# P07_IO_SWITCH_JTAG_MICRO_SD.net
KiCad netlist of a schematic drawn in Altium Designer
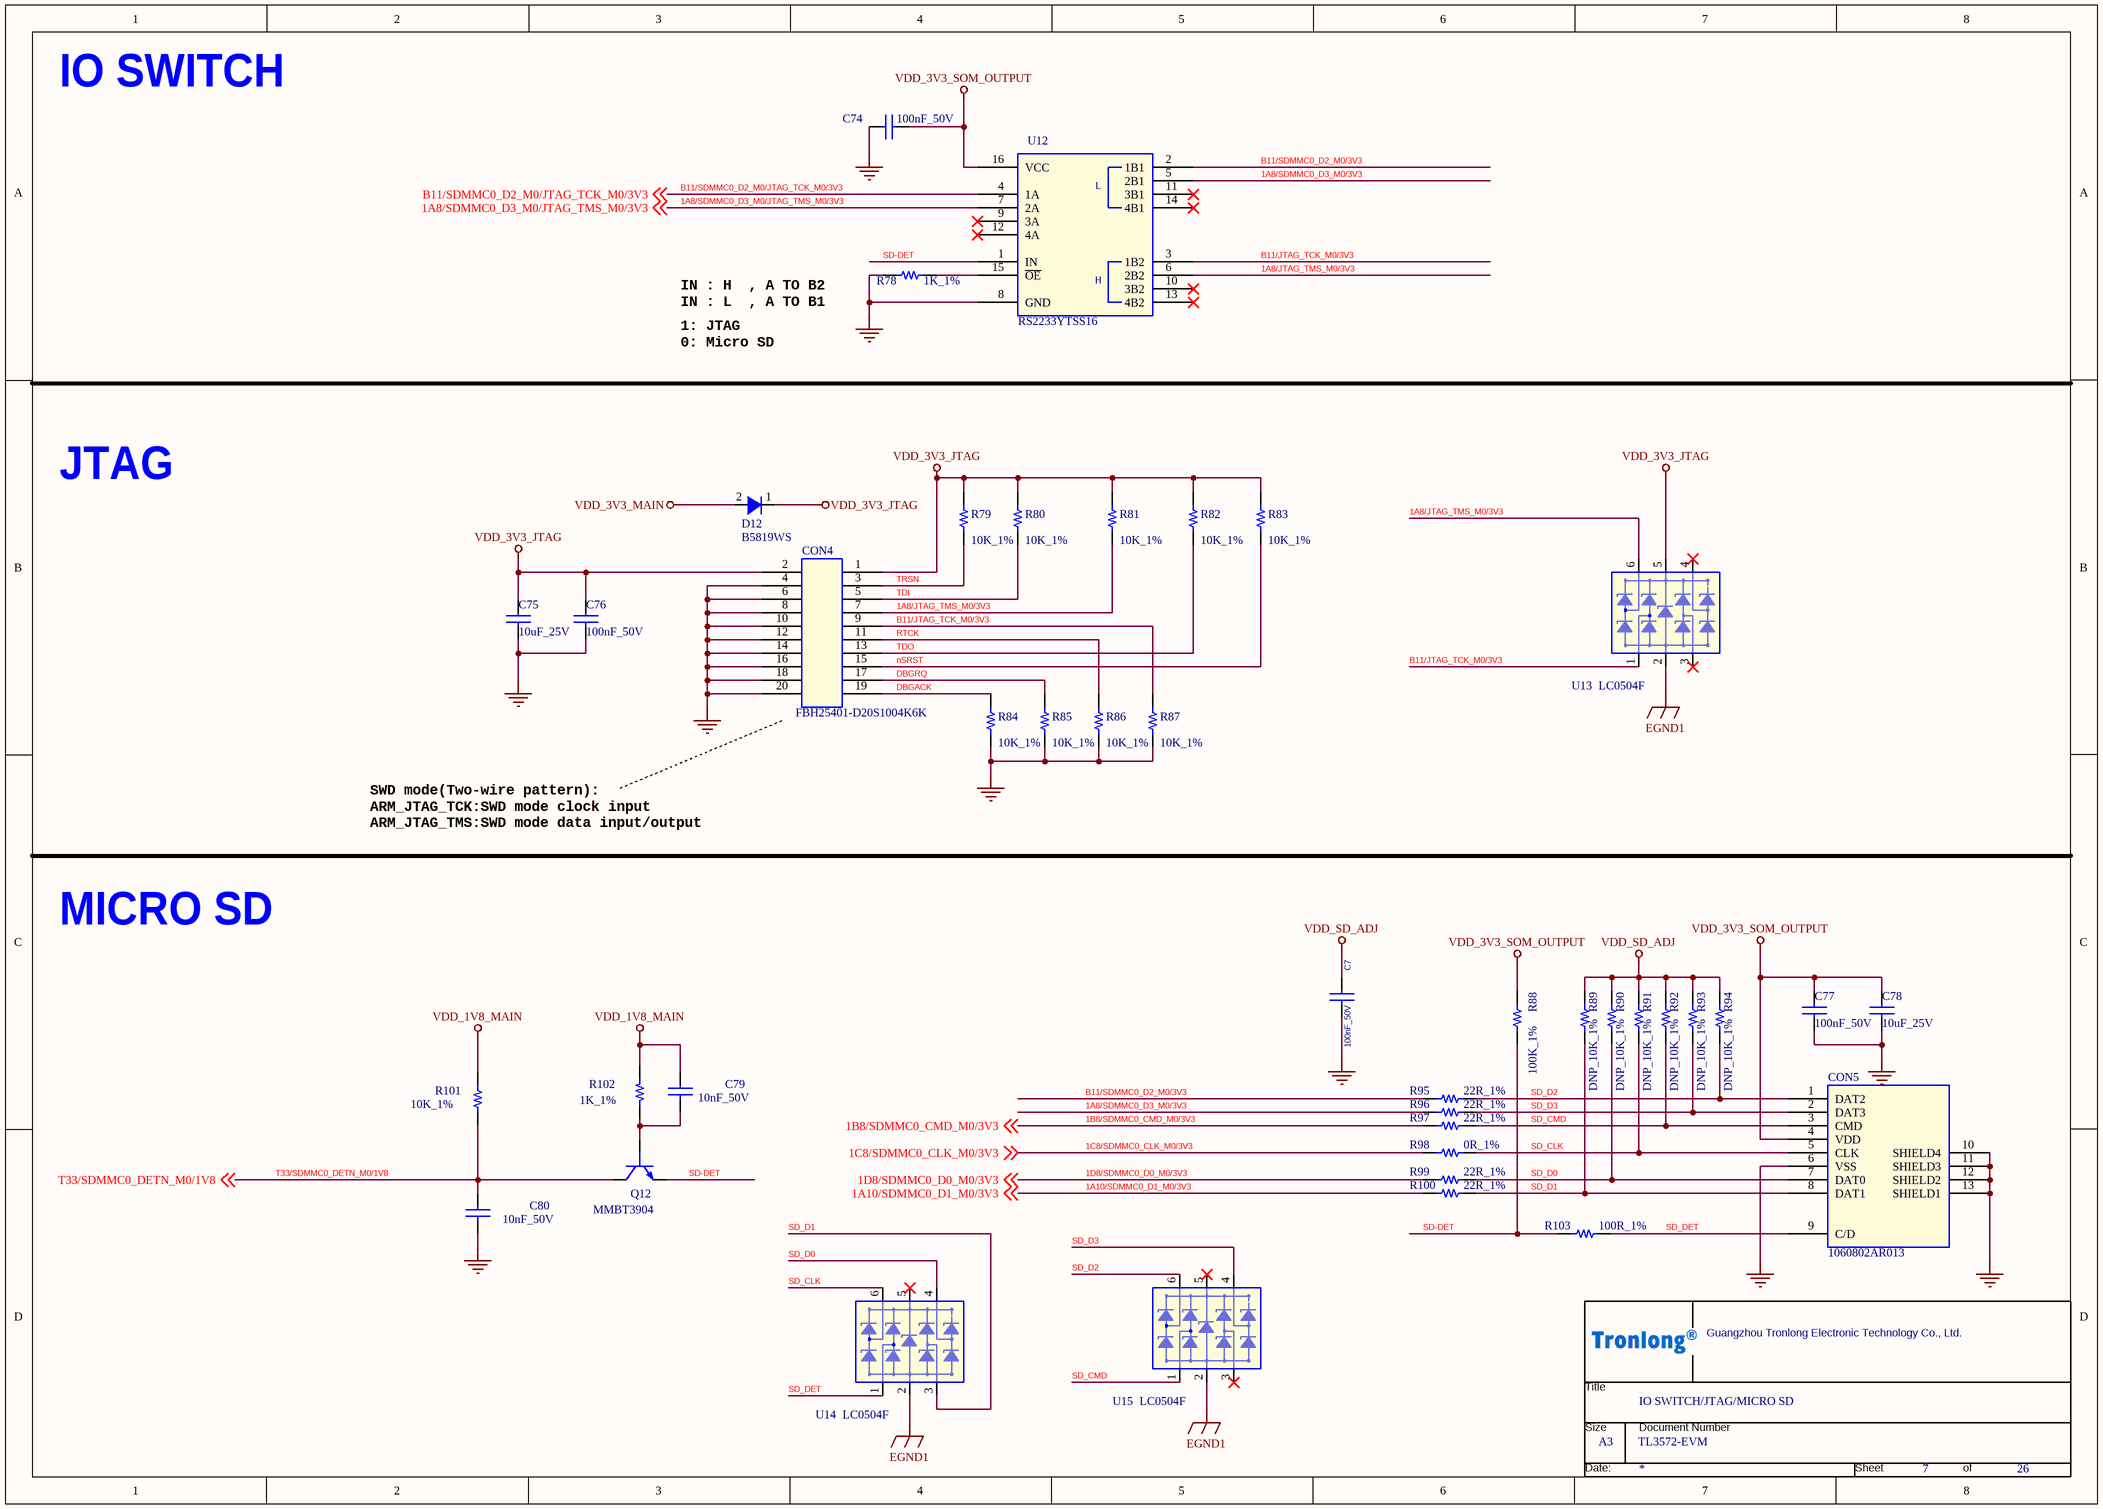
[diagram p0: P07_IO SWITCH_JTAG_MICRO SD.SchDoc]

(export (version "E")
  (design (tool "Eeschema 10.0.6"))
  (components
    (comp (ref "*")
      (value "TL_NEW")
      (fields
        (field (name "PAGE COUNT") "26")
        (field (name "PAGE NUMBER") "7")
        (field (name "PAGE SIZE") "A3")
        (field (name "ORGNAME") "Guangzhou Tronlong Electronic Technology Co., Ltd.")
        (field (name "TITLE") "IO SWITCH/JTAG/MICRO SD")
        (field (name "DOC") "TL3572-EVM")
      )
      (libsource (lib "*") (part "TL_NEW"))
    )
    (comp (ref "C7")
      (value "100nF_50V")
      (footprint "C0402")
      (description "贴片陶瓷电容,100nF,10%,50V,X7R")
      (fields
        (field (name "MANUFACTURER PARTNUMBER") "0402B104K500NT")
        (field (name "MANUFACTURER") "广东风华高新科技股份有限公司（FH）")
      )
      (libsource (lib "*") (part "CAP NP_Dup2"))
    )
    (comp (ref "C74")
      (value "100nF_50V")
      (footprint "C0402")
      (description "贴片陶瓷电容,100nF,10%,50V,X7R")
      (fields
        (field (name "MANUFACTURER") "广东风华高新科技股份有限公司（FH）")
        (field (name "MANUFACTURER PARTNUMBER") "0402B104K500NT")
      )
      (libsource (lib "*") (part "CAP NP_Dup2"))
    )
    (comp (ref "C75")
      (value "10uF_25V")
      (footprint "C0603")
      (description "贴片陶瓷电容,10uF,20%,25V,X5R")
      (fields
        (field (name "MANUFACTURER PARTNUMBER") "0603X106M250NT")
        (field (name "MANUFACTURER") "广东风华高新科技股份有限公司（FH）")
      )
      (libsource (lib "*") (part "CAP NP_Dup2"))
    )
    (comp (ref "C76")
      (value "100nF_50V")
      (footprint "C0402")
      (description "贴片陶瓷电容,100nF,10%,50V,X7R")
      (fields
        (field (name "MANUFACTURER") "广东风华高新科技股份有限公司（FH）")
        (field (name "MANUFACTURER PARTNUMBER") "0402B104K500NT")
      )
      (libsource (lib "*") (part "CAP NP_Dup2"))
    )
    (comp (ref "C77")
      (value "100nF_50V")
      (footprint "C0402")
      (description "贴片陶瓷电容,100nF,10%,50V,X7R")
      (fields
        (field (name "MANUFACTURER") "广东风华高新科技股份有限公司（FH）")
        (field (name "MANUFACTURER PARTNUMBER") "0402B104K500NT")
      )
      (libsource (lib "*") (part "CAP NP_Dup2"))
    )
    (comp (ref "C78")
      (value "10uF_25V")
      (footprint "C0603")
      (description "贴片陶瓷电容,10uF,20%,25V,X5R")
      (fields
        (field (name "MANUFACTURER PARTNUMBER") "0603X106M250NT")
        (field (name "MANUFACTURER") "广东风华高新科技股份有限公司（FH）")
      )
      (libsource (lib "*") (part "CAP NP_Dup2"))
    )
    (comp (ref "C79")
      (value "10nF_50V")
      (footprint "C0402")
      (description "贴片陶瓷电容,10nF,10%,50V,X7R")
      (fields
        (field (name "MANUFACTURER PARTNUMBER") "0402B103K500NT")
        (field (name "MANUFACTURER") "广东风华高新科技股份有限公司（FH）")
      )
      (libsource (lib "*") (part "CAP NP_Dup3"))
    )
    (comp (ref "C80")
      (value "10nF_50V")
      (footprint "C0402")
      (description "贴片陶瓷电容,10nF,10%,50V,X7R")
      (fields
        (field (name "MANUFACTURER PARTNUMBER") "0402B103K500NT")
        (field (name "MANUFACTURER") "广东风华高新科技股份有限公司（FH）")
      )
      (libsource (lib "*") (part "CAP NP_Dup3"))
    )
    (comp (ref "CON4")
      (value "FBH25401-D20S1004K6K")
      (footprint "con_2d54_2x10_th_box_90")
      (description "简易牛角座,2x10P,2.54mm,公座,黑色,180度")
      (fields (field (name "MANUFACTURER") "深圳特思嘉工业电子有限公司（TXGA）"))
      (libsource (lib "*") (part "CON20A"))
    )
    (comp (ref "CON5")
      (value "1060802AR013")
      (footprint "CON_TF_CARD")
      (description "Micro SD卡座,9P,自弹,贴片")
      (fields (field (name "MANUFACTURER") "广州高炬电子科技有限公司（gorchi）"))
      (libsource (lib "*") (part "PROCONN SDC009-52-D_3"))
    )
    (comp (ref "D12")
      (value "B5819WS")
      (footprint "SOD-323")
      (description "肖特基二极管,VR=40V,IF=1A,VF=0.6V@1A")
      (fields (field (name "MFR") "On Semiconductor") (field (name "TIINTPARTNUMBER") "1E0013"))
      (libsource (lib "*") (part "Diode200mA250V_2"))
    )
    (comp (ref "Q12")
      (value "MMBT3904")
      (footprint "SOT23-3_DBZ3")
      (description "BJT,NPN,Vceo=40V,Ic=200mA,fT=300MHz,PD=200mW")
      (fields (field (name "MANUFACTURER") "江苏长晶科技股份有限公司（JSCJ）"))
      (libsource (lib "*") (part "MMBT3904/SOT"))
    )
    (comp (ref "R78")
      (value "1K_1%")
      (footprint "R0603")
      (description "贴片电阻,1K,±1%,1/10W")
      (fields
        (field (name "MANUFACTURER") "广东风华高新科技股份有限公司（FH）")
        (field (name "MANUFACTURER PARTNUMBER") "RS-03K1001FT")
      )
      (libsource (lib "*") (part "Resistor_Dup3"))
    )
    (comp (ref "R79")
      (value "10K_1%")
      (footprint "R0402")
      (description "贴片电阻,10K,±1%,1/16W")
      (fields
        (field (name "MANUFACTURER") "广东风华高新科技股份有限公司（FH）")
        (field (name "MANUFACTURER PARTNUMBER") "RC-02K1002FT")
      )
      (libsource (lib "*") (part "Resistor_Dup3"))
    )
    (comp (ref "R80")
      (value "10K_1%")
      (footprint "R0402")
      (description "贴片电阻,10K,±1%,1/16W")
      (fields
        (field (name "MANUFACTURER PARTNUMBER") "RC-02K1002FT")
        (field (name "MANUFACTURER") "广东风华高新科技股份有限公司（FH）")
      )
      (libsource (lib "*") (part "Resistor_Dup3"))
    )
    (comp (ref "R81")
      (value "10K_1%")
      (footprint "R0402")
      (description "贴片电阻,10K,±1%,1/16W")
      (fields
        (field (name "MANUFACTURER PARTNUMBER") "RC-02K1002FT")
        (field (name "MANUFACTURER") "广东风华高新科技股份有限公司（FH）")
      )
      (libsource (lib "*") (part "Resistor_Dup3"))
    )
    (comp (ref "R82")
      (value "10K_1%")
      (footprint "R0402")
      (description "贴片电阻,10K,±1%,1/16W")
      (fields
        (field (name "MANUFACTURER PARTNUMBER") "RC-02K1002FT")
        (field (name "MANUFACTURER") "广东风华高新科技股份有限公司（FH）")
      )
      (libsource (lib "*") (part "Resistor_Dup3"))
    )
    (comp (ref "R83")
      (value "10K_1%")
      (footprint "R0402")
      (description "贴片电阻,10K,±1%,1/16W")
      (fields
        (field (name "MANUFACTURER") "广东风华高新科技股份有限公司（FH）")
        (field (name "MANUFACTURER PARTNUMBER") "RC-02K1002FT")
      )
      (libsource (lib "*") (part "Resistor_Dup3"))
    )
    (comp (ref "R84")
      (value "10K_1%")
      (footprint "R0402")
      (description "贴片电阻,10K,±1%,1/16W")
      (fields
        (field (name "MANUFACTURER") "广东风华高新科技股份有限公司（FH）")
        (field (name "MANUFACTURER PARTNUMBER") "RC-02K1002FT")
      )
      (libsource (lib "*") (part "Resistor_Dup3"))
    )
    (comp (ref "R85")
      (value "10K_1%")
      (footprint "R0402")
      (description "贴片电阻,10K,±1%,1/16W")
      (fields
        (field (name "MANUFACTURER") "广东风华高新科技股份有限公司（FH）")
        (field (name "MANUFACTURER PARTNUMBER") "RC-02K1002FT")
      )
      (libsource (lib "*") (part "Resistor_Dup3"))
    )
    (comp (ref "R86")
      (value "10K_1%")
      (footprint "R0402")
      (description "贴片电阻,10K,±1%,1/16W")
      (fields
        (field (name "MANUFACTURER PARTNUMBER") "RC-02K1002FT")
        (field (name "MANUFACTURER") "广东风华高新科技股份有限公司（FH）")
      )
      (libsource (lib "*") (part "Resistor_Dup3"))
    )
    (comp (ref "R87")
      (value "10K_1%")
      (footprint "R0402")
      (description "贴片电阻,10K,±1%,1/16W")
      (fields
        (field (name "MANUFACTURER PARTNUMBER") "RC-02K1002FT")
        (field (name "MANUFACTURER") "广东风华高新科技股份有限公司（FH）")
      )
      (libsource (lib "*") (part "Resistor_Dup3"))
    )
    (comp (ref "R88")
      (value "100K_1%")
      (footprint "R0402")
      (description "RC0402FR-07100KL,0402WGF1003TCE")
      (fields
        (field (name "MANUFACTURER PARTNUMBER") "100K,±1%,R0402,≥1/16W")
        (field (name "MANUFACTURER") "广州创龙")
      )
      (libsource (lib "*") (part "Resistor_Dup3"))
    )
    (comp (ref "R89")
      (value "DNP_10K_1%")
      (footprint "R0402")
      (description "贴片电阻,10K,±1%,1/16W")
      (fields
        (field (name "MANUFACTURER") "广东风华高新科技股份有限公司（FH）")
        (field (name "MANUFACTURER PARTNUMBER") "RC-02K1002FT")
      )
      (libsource (lib "*") (part "Resistor_Dup3"))
    )
    (comp (ref "R90")
      (value "DNP_10K_1%")
      (footprint "R0402")
      (description "贴片电阻,10K,±1%,1/16W")
      (fields
        (field (name "MANUFACTURER") "广东风华高新科技股份有限公司（FH）")
        (field (name "MANUFACTURER PARTNUMBER") "RC-02K1002FT")
      )
      (libsource (lib "*") (part "Resistor_Dup3"))
    )
    (comp (ref "R91")
      (value "DNP_10K_1%")
      (footprint "R0402")
      (description "贴片电阻,10K,±1%,1/16W")
      (fields
        (field (name "MANUFACTURER") "广东风华高新科技股份有限公司（FH）")
        (field (name "MANUFACTURER PARTNUMBER") "RC-02K1002FT")
      )
      (libsource (lib "*") (part "Resistor_Dup3"))
    )
    (comp (ref "R92")
      (value "DNP_10K_1%")
      (footprint "R0402")
      (description "贴片电阻,10K,±1%,1/16W")
      (fields
        (field (name "MANUFACTURER PARTNUMBER") "RC-02K1002FT")
        (field (name "MANUFACTURER") "广东风华高新科技股份有限公司（FH）")
      )
      (libsource (lib "*") (part "Resistor_Dup3"))
    )
    (comp (ref "R93")
      (value "DNP_10K_1%")
      (footprint "R0402")
      (description "贴片电阻,10K,±1%,1/16W")
      (fields
        (field (name "MANUFACTURER") "广东风华高新科技股份有限公司（FH）")
        (field (name "MANUFACTURER PARTNUMBER") "RC-02K1002FT")
      )
      (libsource (lib "*") (part "Resistor_Dup3"))
    )
    (comp (ref "R94")
      (value "DNP_10K_1%")
      (footprint "R0402")
      (description "贴片电阻,10K,±1%,1/16W")
      (fields
        (field (name "MANUFACTURER") "广东风华高新科技股份有限公司（FH）")
        (field (name "MANUFACTURER PARTNUMBER") "RC-02K1002FT")
      )
      (libsource (lib "*") (part "Resistor_Dup3"))
    )
    (comp (ref "R95")
      (value "22R_1%")
      (footprint "R0402")
      (description "贴片电阻,22R,±1%,1/16W")
      (fields
        (field (name "MANUFACTURER PARTNUMBER") "RC-02K22R0FT")
        (field (name "MANUFACTURER") "广东风华高新科技股份有限公司（FH）")
      )
      (libsource (lib "*") (part "Resistor_Dup3"))
    )
    (comp (ref "R96")
      (value "22R_1%")
      (footprint "R0402")
      (description "贴片电阻,22R,±1%,1/16W")
      (fields
        (field (name "MANUFACTURER PARTNUMBER") "RC-02K22R0FT")
        (field (name "MANUFACTURER") "广东风华高新科技股份有限公司（FH）")
      )
      (libsource (lib "*") (part "Resistor_Dup3"))
    )
    (comp (ref "R97")
      (value "22R_1%")
      (footprint "R0402")
      (description "贴片电阻,22R,±1%,1/16W")
      (fields
        (field (name "MANUFACTURER PARTNUMBER") "RC-02K22R0FT")
        (field (name "MANUFACTURER") "广东风华高新科技股份有限公司（FH）")
      )
      (libsource (lib "*") (part "Resistor_Dup3"))
    )
    (comp (ref "R98")
      (value "0R_1%")
      (footprint "R0402")
      (description "贴片电阻,0R,±1%,1/16W")
      (fields
        (field (name "MANUFACTURER") "广东风华高新科技股份有限公司（FH）")
        (field (name "MANUFACTURER PARTNUMBER") "RC-02000FT")
      )
      (libsource (lib "*") (part "Resistor_Dup3"))
    )
    (comp (ref "R99")
      (value "22R_1%")
      (footprint "R0402")
      (description "贴片电阻,22R,±1%,1/16W")
      (fields
        (field (name "MANUFACTURER") "广东风华高新科技股份有限公司（FH）")
        (field (name "MANUFACTURER PARTNUMBER") "RC-02K22R0FT")
      )
      (libsource (lib "*") (part "Resistor_Dup3"))
    )
    (comp (ref "R100")
      (value "22R_1%")
      (footprint "R0402")
      (description "贴片电阻,22R,±1%,1/16W")
      (fields
        (field (name "MANUFACTURER PARTNUMBER") "RC-02K22R0FT")
        (field (name "MANUFACTURER") "广东风华高新科技股份有限公司（FH）")
      )
      (libsource (lib "*") (part "Resistor_Dup3"))
    )
    (comp (ref "R101")
      (value "10K_1%")
      (footprint "R0402")
      (description "贴片电阻,10K,±1%,1/16W")
      (fields
        (field (name "MANUFACTURER") "广东风华高新科技股份有限公司（FH）")
        (field (name "MANUFACTURER PARTNUMBER") "RC-02K1002FT")
      )
      (libsource (lib "*") (part "Resistor_Dup4"))
    )
    (comp (ref "R102")
      (value "1K_1%")
      (footprint "R0603")
      (description "贴片电阻,1K,±1%,1/10W")
      (fields
        (field (name "MANUFACTURER PARTNUMBER") "RS-03K1001FT")
        (field (name "MANUFACTURER") "广东风华高新科技股份有限公司（FH）")
      )
      (libsource (lib "*") (part "Resistor_Dup4"))
    )
    (comp (ref "R103")
      (value "100R_1%")
      (footprint "R0402")
      (description "贴片电阻,100R,±1%,1/16W")
      (fields
        (field (name "MANUFACTURER") "广东风华高新科技股份有限公司（FH）")
        (field (name "MANUFACTURER PARTNUMBER") "RC-02K1000FT")
      )
      (libsource (lib "*") (part "Resistor_Dup4"))
    )
    (comp (ref "U12")
      (value "RS2233YTSS16")
      (footprint "TSSOP16")
      (description "4通道模拟开关")
      (fields (field (name "MANUFACTURER") "江苏润石科技有限公司（RUNIC）"))
      (libsource (lib "*") (part "TS3A5018DR_2"))
    )
    (comp (ref "U13")
      (value "LC0504F")
      (footprint "SOT363")
      (description "ESD二极管,VRWM=5V,VBR=6V,四组,单向,8KV,15KV")
      (fields
        (field (name "MANUFACTURER PART NUMBER") "PRTR5V0U4Y")
        (field (name "MANUFACTURER") "上海雷卯电子科技有限公司（Leiditech）")
      )
      (libsource (lib "*") (part "PRTR5V0U4Y_0"))
    )
    (comp (ref "U14")
      (value "LC0504F")
      (footprint "SOT363")
      (description "ESD二极管,VRWM=5V,VBR=6V,四组,单向,8KV,15KV")
      (fields
        (field (name "MANUFACTURER") "上海雷卯电子科技有限公司（Leiditech）")
        (field (name "MANUFACTURER PART NUMBER") "PRTR5V0U4Y")
      )
      (libsource (lib "*") (part "PRTR5V0U4Y_0"))
    )
    (comp (ref "U15")
      (value "LC0504F")
      (footprint "SOT363")
      (description "ESD二极管,VRWM=5V,VBR=6V,四组,单向,8KV,15KV")
      (fields
        (field (name "MANUFACTURER PART NUMBER") "PRTR5V0U4Y")
        (field (name "MANUFACTURER") "上海雷卯电子科技有限公司（Leiditech）")
      )
      (libsource (lib "*") (part "PRTR5V0U4Y_0"))
    )
  )
  (nets
    (net (code "1") (name "/1A8{slash}JTAG_TMS_M0{slash}3V3") (class "Default")
      (node (ref "CON4") (pin "7") (pinfunction "7_7") (pintype "passive"))
      (node (ref "R81") (pin "2") (pinfunction "2_2") (pintype "passive"))
      (node (ref "U12") (pin "6") (pinfunction "2B2_6") (pintype "passive"))
      (node (ref "U13") (pin "6") (pinfunction "6_6") (pintype "passive"))
    )
    (net (code "2") (name "/1A8{slash}SDMMC0_D3_M0{slash}3V3") (class "Default")
      (node (ref "R96") (pin "1") (pinfunction "1_1") (pintype "passive"))
      (node (ref "U12") (pin "5") (pinfunction "2B1_5") (pintype "passive"))
    )
    (net (code "3") (name "/B11{slash}JTAG_TCK_M0{slash}3V3") (class "Default")
      (node (ref "CON4") (pin "9") (pinfunction "9_9") (pintype "passive"))
      (node (ref "R87") (pin "1") (pinfunction "1_1") (pintype "passive"))
      (node (ref "U12") (pin "3") (pinfunction "1B2_3") (pintype "passive"))
      (node (ref "U13") (pin "1") (pinfunction "1_1") (pintype "passive"))
    )
    (net (code "4") (name "/B11{slash}SDMMC0_D2_M0{slash}3V3") (class "Default")
      (node (ref "R95") (pin "1") (pinfunction "1_1") (pintype "passive"))
      (node (ref "U12") (pin "2") (pinfunction "1B1_2") (pintype "passive"))
    )
    (net (code "5") (name "/DBGACK") (class "Default")
      (node (ref "CON4") (pin "19") (pinfunction "19_19") (pintype "passive"))
      (node (ref "R84") (pin "1") (pinfunction "1_1") (pintype "passive"))
    )
    (net (code "6") (name "/DBGRQ") (class "Default")
      (node (ref "CON4") (pin "17") (pinfunction "17_17") (pintype "passive"))
      (node (ref "R85") (pin "1") (pinfunction "1_1") (pintype "passive"))
    )
    (net (code "7") (name "/RTCK") (class "Default")
      (node (ref "CON4") (pin "11") (pinfunction "11_11") (pintype "passive"))
      (node (ref "R86") (pin "1") (pinfunction "1_1") (pintype "passive"))
    )
    (net (code "8") (name "/SD-DET") (class "Default")
      (node (ref "Q12") (pin "2") (pinfunction "E_2") (pintype "passive"))
      (node (ref "R103") (pin "1") (pinfunction "1_1") (pintype "passive"))
      (node (ref "R88") (pin "2") (pinfunction "2_2") (pintype "passive"))
      (node (ref "U12") (pin "1") (pinfunction "IN_1") (pintype "passive"))
    )
    (net (code "9") (name "/SD_CLK") (class "Default")
      (node (ref "CON5") (pin "5") (pinfunction "CLK_5") (pintype "passive"))
      (node (ref "R91") (pin "2") (pinfunction "2_2") (pintype "passive"))
      (node (ref "R98") (pin "2") (pinfunction "2_2") (pintype "passive"))
      (node (ref "U14") (pin "6") (pinfunction "6_6") (pintype "passive"))
    )
    (net (code "10") (name "/SD_CMD") (class "Default")
      (node (ref "CON5") (pin "3") (pinfunction "CMD_3") (pintype "passive"))
      (node (ref "R92") (pin "2") (pinfunction "2_2") (pintype "passive"))
      (node (ref "R97") (pin "2") (pinfunction "2_2") (pintype "passive"))
      (node (ref "U15") (pin "1") (pinfunction "1_1") (pintype "passive"))
    )
    (net (code "11") (name "/SD_D0") (class "Default")
      (node (ref "CON5") (pin "7") (pinfunction "DAT0_7") (pintype "passive"))
      (node (ref "R90") (pin "2") (pinfunction "2_2") (pintype "passive"))
      (node (ref "R99") (pin "2") (pinfunction "2_2") (pintype "passive"))
      (node (ref "U14") (pin "4") (pinfunction "4_4") (pintype "passive"))
    )
    (net (code "12") (name "/SD_D1") (class "Default")
      (node (ref "CON5") (pin "8") (pinfunction "DAT1_8") (pintype "passive"))
      (node (ref "R100") (pin "2") (pinfunction "2_2") (pintype "passive"))
      (node (ref "R89") (pin "2") (pinfunction "2_2") (pintype "passive"))
      (node (ref "U14") (pin "3") (pinfunction "3_3") (pintype "passive"))
    )
    (net (code "13") (name "/SD_D2") (class "Default")
      (node (ref "CON5") (pin "1") (pinfunction "DAT2_1") (pintype "passive"))
      (node (ref "R94") (pin "2") (pinfunction "2_2") (pintype "passive"))
      (node (ref "R95") (pin "2") (pinfunction "2_2") (pintype "passive"))
      (node (ref "U15") (pin "6") (pinfunction "6_6") (pintype "passive"))
    )
    (net (code "14") (name "/SD_D3") (class "Default")
      (node (ref "CON5") (pin "2") (pinfunction "DAT3_2") (pintype "passive"))
      (node (ref "R93") (pin "2") (pinfunction "2_2") (pintype "passive"))
      (node (ref "R96") (pin "2") (pinfunction "2_2") (pintype "passive"))
      (node (ref "U15") (pin "4") (pinfunction "4_4") (pintype "passive"))
    )
    (net (code "15") (name "/SD_DET") (class "Default")
      (node (ref "CON5") (pin "9") (pinfunction "C/D_9") (pintype "passive"))
      (node (ref "R103") (pin "2") (pinfunction "2_2") (pintype "passive"))
      (node (ref "U14") (pin "1") (pinfunction "1_1") (pintype "passive"))
    )
    (net (code "16") (name "/TDI") (class "Default")
      (node (ref "CON4") (pin "5") (pinfunction "5_5") (pintype "passive"))
      (node (ref "R80") (pin "2") (pinfunction "2_2") (pintype "passive"))
    )
    (net (code "17") (name "/TDO") (class "Default")
      (node (ref "CON4") (pin "13") (pinfunction "13_13") (pintype "passive"))
      (node (ref "R82") (pin "2") (pinfunction "2_2") (pintype "passive"))
    )
    (net (code "18") (name "/TRSN") (class "Default")
      (node (ref "CON4") (pin "3") (pinfunction "3_3") (pintype "passive"))
      (node (ref "R79") (pin "2") (pinfunction "2_2") (pintype "passive"))
    )
    (net (code "19") (name "/nSRST") (class "Default")
      (node (ref "CON4") (pin "15") (pinfunction "15_15") (pintype "passive"))
      (node (ref "R83") (pin "2") (pinfunction "2_2") (pintype "passive"))
    )
    (net (code "20") (name "1A8{slash}SDMMC0_D3_M0{slash}JTAG_TMS_M0{slash}3V3") (class "Default")
      (node (ref "U12") (pin "7") (pinfunction "2A_7") (pintype "passive"))
    )
    (net (code "21") (name "1A10{slash}SDMMC0_D1_M0{slash}3V3") (class "Default")
      (node (ref "R100") (pin "1") (pinfunction "1_1") (pintype "passive"))
    )
    (net (code "22") (name "1B8{slash}SDMMC0_CMD_M0{slash}3V3") (class "Default")
      (node (ref "R97") (pin "1") (pinfunction "1_1") (pintype "passive"))
    )
    (net (code "23") (name "1C8{slash}SDMMC0_CLK_M0{slash}3V3") (class "Default")
      (node (ref "R98") (pin "1") (pinfunction "1_1") (pintype "passive"))
    )
    (net (code "24") (name "1D8{slash}SDMMC0_D0_M0{slash}3V3") (class "Default")
      (node (ref "R99") (pin "1") (pinfunction "1_1") (pintype "passive"))
    )
    (net (code "25") (name "B11{slash}SDMMC0_D2_M0{slash}JTAG_TCK_M0{slash}3V3") (class "Default")
      (node (ref "U12") (pin "4") (pinfunction "1A_4") (pintype "passive"))
    )
    (net (code "26") (name "EGND1") (class "Default")
      (node (ref "U13") (pin "2") (pinfunction "2_2") (pintype "passive"))
      (node (ref "U14") (pin "2") (pinfunction "2_2") (pintype "passive"))
      (node (ref "U15") (pin "2") (pinfunction "2_2") (pintype "passive"))
    )
    (net (code "27") (name "GND") (class "Default")
      (node (ref "C7") (pin "2") (pinfunction "2_2") (pintype "passive"))
      (node (ref "C74") (pin "1") (pinfunction "1_1") (pintype "passive"))
      (node (ref "C75") (pin "2") (pinfunction "2_2") (pintype "passive"))
      (node (ref "C76") (pin "2") (pinfunction "2_2") (pintype "passive"))
      (node (ref "C77") (pin "2") (pinfunction "2_2") (pintype "passive"))
      (node (ref "C78") (pin "2") (pinfunction "2_2") (pintype "passive"))
      (node (ref "C80") (pin "2") (pinfunction "2_2") (pintype "passive"))
      (node (ref "CON4") (pin "10") (pinfunction "10_10") (pintype "passive"))
      (node (ref "CON4") (pin "12") (pinfunction "12_12") (pintype "passive"))
      (node (ref "CON4") (pin "14") (pinfunction "14_14") (pintype "passive"))
      (node (ref "CON4") (pin "16") (pinfunction "16_16") (pintype "passive"))
      (node (ref "CON4") (pin "18") (pinfunction "18_18") (pintype "passive"))
      (node (ref "CON4") (pin "20") (pinfunction "20_20") (pintype "passive"))
      (node (ref "CON4") (pin "4") (pinfunction "4_4") (pintype "passive"))
      (node (ref "CON4") (pin "6") (pinfunction "6_6") (pintype "passive"))
      (node (ref "CON4") (pin "8") (pinfunction "8_8") (pintype "passive"))
      (node (ref "CON5") (pin "10") (pinfunction "SHIELD4_10") (pintype "power_in"))
      (node (ref "CON5") (pin "11") (pinfunction "SHIELD3_11") (pintype "passive"))
      (node (ref "CON5") (pin "12") (pinfunction "SHIELD2_12") (pintype "passive"))
      (node (ref "CON5") (pin "13") (pinfunction "SHIELD1_13") (pintype "passive"))
      (node (ref "CON5") (pin "6") (pinfunction "VSS_6") (pintype "power_in"))
      (node (ref "R78") (pin "2") (pinfunction "2_2") (pintype "passive"))
      (node (ref "R84") (pin "2") (pinfunction "2_2") (pintype "passive"))
      (node (ref "R85") (pin "2") (pinfunction "2_2") (pintype "passive"))
      (node (ref "R86") (pin "2") (pinfunction "2_2") (pintype "passive"))
      (node (ref "R87") (pin "2") (pinfunction "2_2") (pintype "passive"))
      (node (ref "U12") (pin "8") (pinfunction "GND_8") (pintype "power_in"))
    )
    (net (code "28") (name "Net-(Q12-B)") (class "Default")
      (node (ref "C79") (pin "2") (pinfunction "2_2") (pintype "passive"))
      (node (ref "Q12") (pin "1") (pinfunction "B_1") (pintype "passive"))
      (node (ref "R102") (pin "2") (pinfunction "2_2") (pintype "passive"))
    )
    (net (code "29") (name "Net-(U12-~{OE})") (class "Default")
      (node (ref "R78") (pin "1") (pinfunction "1_1") (pintype "passive"))
      (node (ref "U12") (pin "15") (pinfunction "~{OE}_15") (pintype "passive"))
    )
    (net (code "30") (name "T33{slash}SDMMC0_DETN_M0{slash}1V8") (class "Default")
      (node (ref "C80") (pin "1") (pinfunction "1_1") (pintype "passive"))
      (node (ref "Q12") (pin "3") (pinfunction "C_3") (pintype "passive"))
      (node (ref "R101") (pin "2") (pinfunction "2_2") (pintype "passive"))
    )
    (net (code "31") (name "VDD_1V8_MAIN") (class "Default")
      (node (ref "C79") (pin "1") (pinfunction "1_1") (pintype "passive"))
      (node (ref "R101") (pin "1") (pinfunction "1_1") (pintype "passive"))
      (node (ref "R102") (pin "1") (pinfunction "1_1") (pintype "passive"))
    )
    (net (code "32") (name "VDD_3V3_JTAG") (class "Default")
      (node (ref "C75") (pin "1") (pinfunction "1_1") (pintype "passive"))
      (node (ref "C76") (pin "1") (pinfunction "1_1") (pintype "passive"))
      (node (ref "CON4") (pin "1") (pinfunction "1_1") (pintype "passive"))
      (node (ref "CON4") (pin "2") (pinfunction "2_2") (pintype "passive"))
      (node (ref "D12") (pin "1") (pinfunction "Anode_1") (pintype "passive"))
      (node (ref "R79") (pin "1") (pinfunction "1_1") (pintype "passive"))
      (node (ref "R80") (pin "1") (pinfunction "1_1") (pintype "passive"))
      (node (ref "R81") (pin "1") (pinfunction "1_1") (pintype "passive"))
      (node (ref "R82") (pin "1") (pinfunction "1_1") (pintype "passive"))
      (node (ref "R83") (pin "1") (pinfunction "1_1") (pintype "passive"))
      (node (ref "U13") (pin "5") (pinfunction "5_5") (pintype "passive"))
    )
    (net (code "33") (name "VDD_3V3_MAIN") (class "Default")
      (node (ref "D12") (pin "2") (pinfunction "Cathode_2") (pintype "passive"))
    )
    (net (code "34") (name "VDD_3V3_SOM_OUTPUT") (class "Default")
      (node (ref "C74") (pin "2") (pinfunction "2_2") (pintype "passive"))
      (node (ref "C77") (pin "1") (pinfunction "1_1") (pintype "passive"))
      (node (ref "C78") (pin "1") (pinfunction "1_1") (pintype "passive"))
      (node (ref "CON5") (pin "4") (pinfunction "VDD_4") (pintype "power_in"))
      (node (ref "R88") (pin "1") (pinfunction "1_1") (pintype "passive"))
      (node (ref "U12") (pin "16") (pinfunction "VCC_16") (pintype "power_in"))
    )
    (net (code "35") (name "VDD_SD_ADJ") (class "Default")
      (node (ref "C7") (pin "1") (pinfunction "1_1") (pintype "passive"))
      (node (ref "R89") (pin "1") (pinfunction "1_1") (pintype "passive"))
      (node (ref "R90") (pin "1") (pinfunction "1_1") (pintype "passive"))
      (node (ref "R91") (pin "1") (pinfunction "1_1") (pintype "passive"))
      (node (ref "R92") (pin "1") (pinfunction "1_1") (pintype "passive"))
      (node (ref "R93") (pin "1") (pinfunction "1_1") (pintype "passive"))
      (node (ref "R94") (pin "1") (pinfunction "1_1") (pintype "passive"))
    )
    (net (code "36") (name "unconnected-(U12-3A-Pad9)") (class "Default")
      (node (ref "U12") (pin "9") (pinfunction "3A_9") (pintype "passive+no_connect"))
    )
    (net (code "37") (name "unconnected-(U12-3B1-Pad11)") (class "Default")
      (node (ref "U12") (pin "11") (pinfunction "3B1_11") (pintype "passive+no_connect"))
    )
    (net (code "38") (name "unconnected-(U12-3B2-Pad10)") (class "Default")
      (node (ref "U12") (pin "10") (pinfunction "3B2_10") (pintype "passive+no_connect"))
    )
    (net (code "39") (name "unconnected-(U12-4A-Pad12)") (class "Default")
      (node (ref "U12") (pin "12") (pinfunction "4A_12") (pintype "passive+no_connect"))
    )
    (net (code "40") (name "unconnected-(U12-4B1-Pad14)") (class "Default")
      (node (ref "U12") (pin "14") (pinfunction "4B1_14") (pintype "passive+no_connect"))
    )
    (net (code "41") (name "unconnected-(U12-4B2-Pad13)") (class "Default")
      (node (ref "U12") (pin "13") (pinfunction "4B2_13") (pintype "passive+no_connect"))
    )
    (net (code "42") (name "unconnected-(U13-Pad3)") (class "Default")
      (node (ref "U13") (pin "3") (pinfunction "3_3") (pintype "passive+no_connect"))
    )
    (net (code "43") (name "unconnected-(U13-Pad4)") (class "Default")
      (node (ref "U13") (pin "4") (pinfunction "4_4") (pintype "passive+no_connect"))
    )
    (net (code "44") (name "unconnected-(U14-Pad5)") (class "Default")
      (node (ref "U14") (pin "5") (pinfunction "5_5") (pintype "passive+no_connect"))
    )
    (net (code "45") (name "unconnected-(U15-Pad3)") (class "Default")
      (node (ref "U15") (pin "3") (pinfunction "3_3") (pintype "passive+no_connect"))
    )
    (net (code "46") (name "unconnected-(U15-Pad5)") (class "Default")
      (node (ref "U15") (pin "5") (pinfunction "5_5") (pintype "passive+no_connect"))
    )
  )
)
